# Laser785Adapter.net
KiCad netlist of a schematic drawn in EAGLE
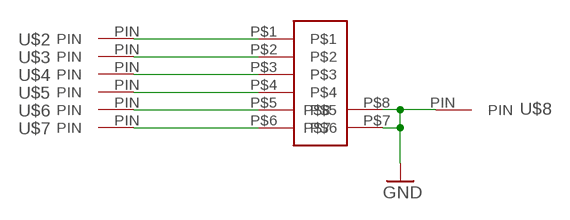
[diagram p0: schematic, sheet 1]

(export (version "E")
  (design (tool "Eeschema 10.0.6"))
  (components
    (comp (ref "U$1")
      (value "MOLEX_5023860670")
      (footprint "eagle-import:MOLEX_5023860670")
      (libsource (lib "eagle-import") (part "MOLEX_5023860670"))
    )
    (comp (ref "U$2")
      (value "PIN")
      (footprint "eagle-import:PIN")
      (libsource (lib "eagle-import") (part "PIN"))
    )
    (comp (ref "U$3")
      (value "PIN")
      (footprint "eagle-import:PIN")
      (libsource (lib "eagle-import") (part "PIN"))
    )
    (comp (ref "U$4")
      (value "PIN")
      (footprint "eagle-import:PIN")
      (libsource (lib "eagle-import") (part "PIN"))
    )
    (comp (ref "U$5")
      (value "PIN")
      (footprint "eagle-import:PIN")
      (libsource (lib "eagle-import") (part "PIN"))
    )
    (comp (ref "U$6")
      (value "PIN")
      (footprint "eagle-import:PIN")
      (libsource (lib "eagle-import") (part "PIN"))
    )
    (comp (ref "U$7")
      (value "PIN")
      (footprint "eagle-import:PIN")
      (libsource (lib "eagle-import") (part "PIN"))
    )
    (comp (ref "U$8")
      (value "PIN")
      (footprint "eagle-import:PIN")
      (libsource (lib "eagle-import") (part "PIN"))
    )
  )
  (nets
    (net (code "1") (name "GND") (class "Default")
      (node (ref "U$1") (pin "P$7") (pinfunction "P$7_P$7") (pintype "bidirectional"))
      (node (ref "U$1") (pin "P$8") (pinfunction "P$8_P$8") (pintype "bidirectional"))
      (node (ref "U$8") (pin "PIN") (pinfunction "PIN_PIN") (pintype "bidirectional"))
    )
    (net (code "2") (name "Net-(U$1-PadP$1)") (class "Default")
      (node (ref "U$1") (pin "P$1") (pinfunction "P$1_P$1") (pintype "bidirectional"))
      (node (ref "U$2") (pin "PIN") (pinfunction "PIN_PIN") (pintype "bidirectional"))
    )
    (net (code "3") (name "Net-(U$1-PadP$2)") (class "Default")
      (node (ref "U$1") (pin "P$2") (pinfunction "P$2_P$2") (pintype "bidirectional"))
      (node (ref "U$3") (pin "PIN") (pinfunction "PIN_PIN") (pintype "bidirectional"))
    )
    (net (code "4") (name "Net-(U$1-PadP$3)") (class "Default")
      (node (ref "U$1") (pin "P$3") (pinfunction "P$3_P$3") (pintype "bidirectional"))
      (node (ref "U$4") (pin "PIN") (pinfunction "PIN_PIN") (pintype "bidirectional"))
    )
    (net (code "5") (name "Net-(U$1-PadP$4)") (class "Default")
      (node (ref "U$1") (pin "P$4") (pinfunction "P$4_P$4") (pintype "bidirectional"))
      (node (ref "U$5") (pin "PIN") (pinfunction "PIN_PIN") (pintype "bidirectional"))
    )
    (net (code "6") (name "Net-(U$1-PadP$5)") (class "Default")
      (node (ref "U$1") (pin "P$5") (pinfunction "P$5_P$5") (pintype "bidirectional"))
      (node (ref "U$6") (pin "PIN") (pinfunction "PIN_PIN") (pintype "bidirectional"))
    )
    (net (code "7") (name "Net-(U$1-PadP$6)") (class "Default")
      (node (ref "U$1") (pin "P$6") (pinfunction "P$6_P$6") (pintype "bidirectional"))
      (node (ref "U$7") (pin "PIN") (pinfunction "PIN_PIN") (pintype "bidirectional"))
    )
  )
)
